# RedpiLite.net
KiCad netlist of a schematic drawn in EAGLE
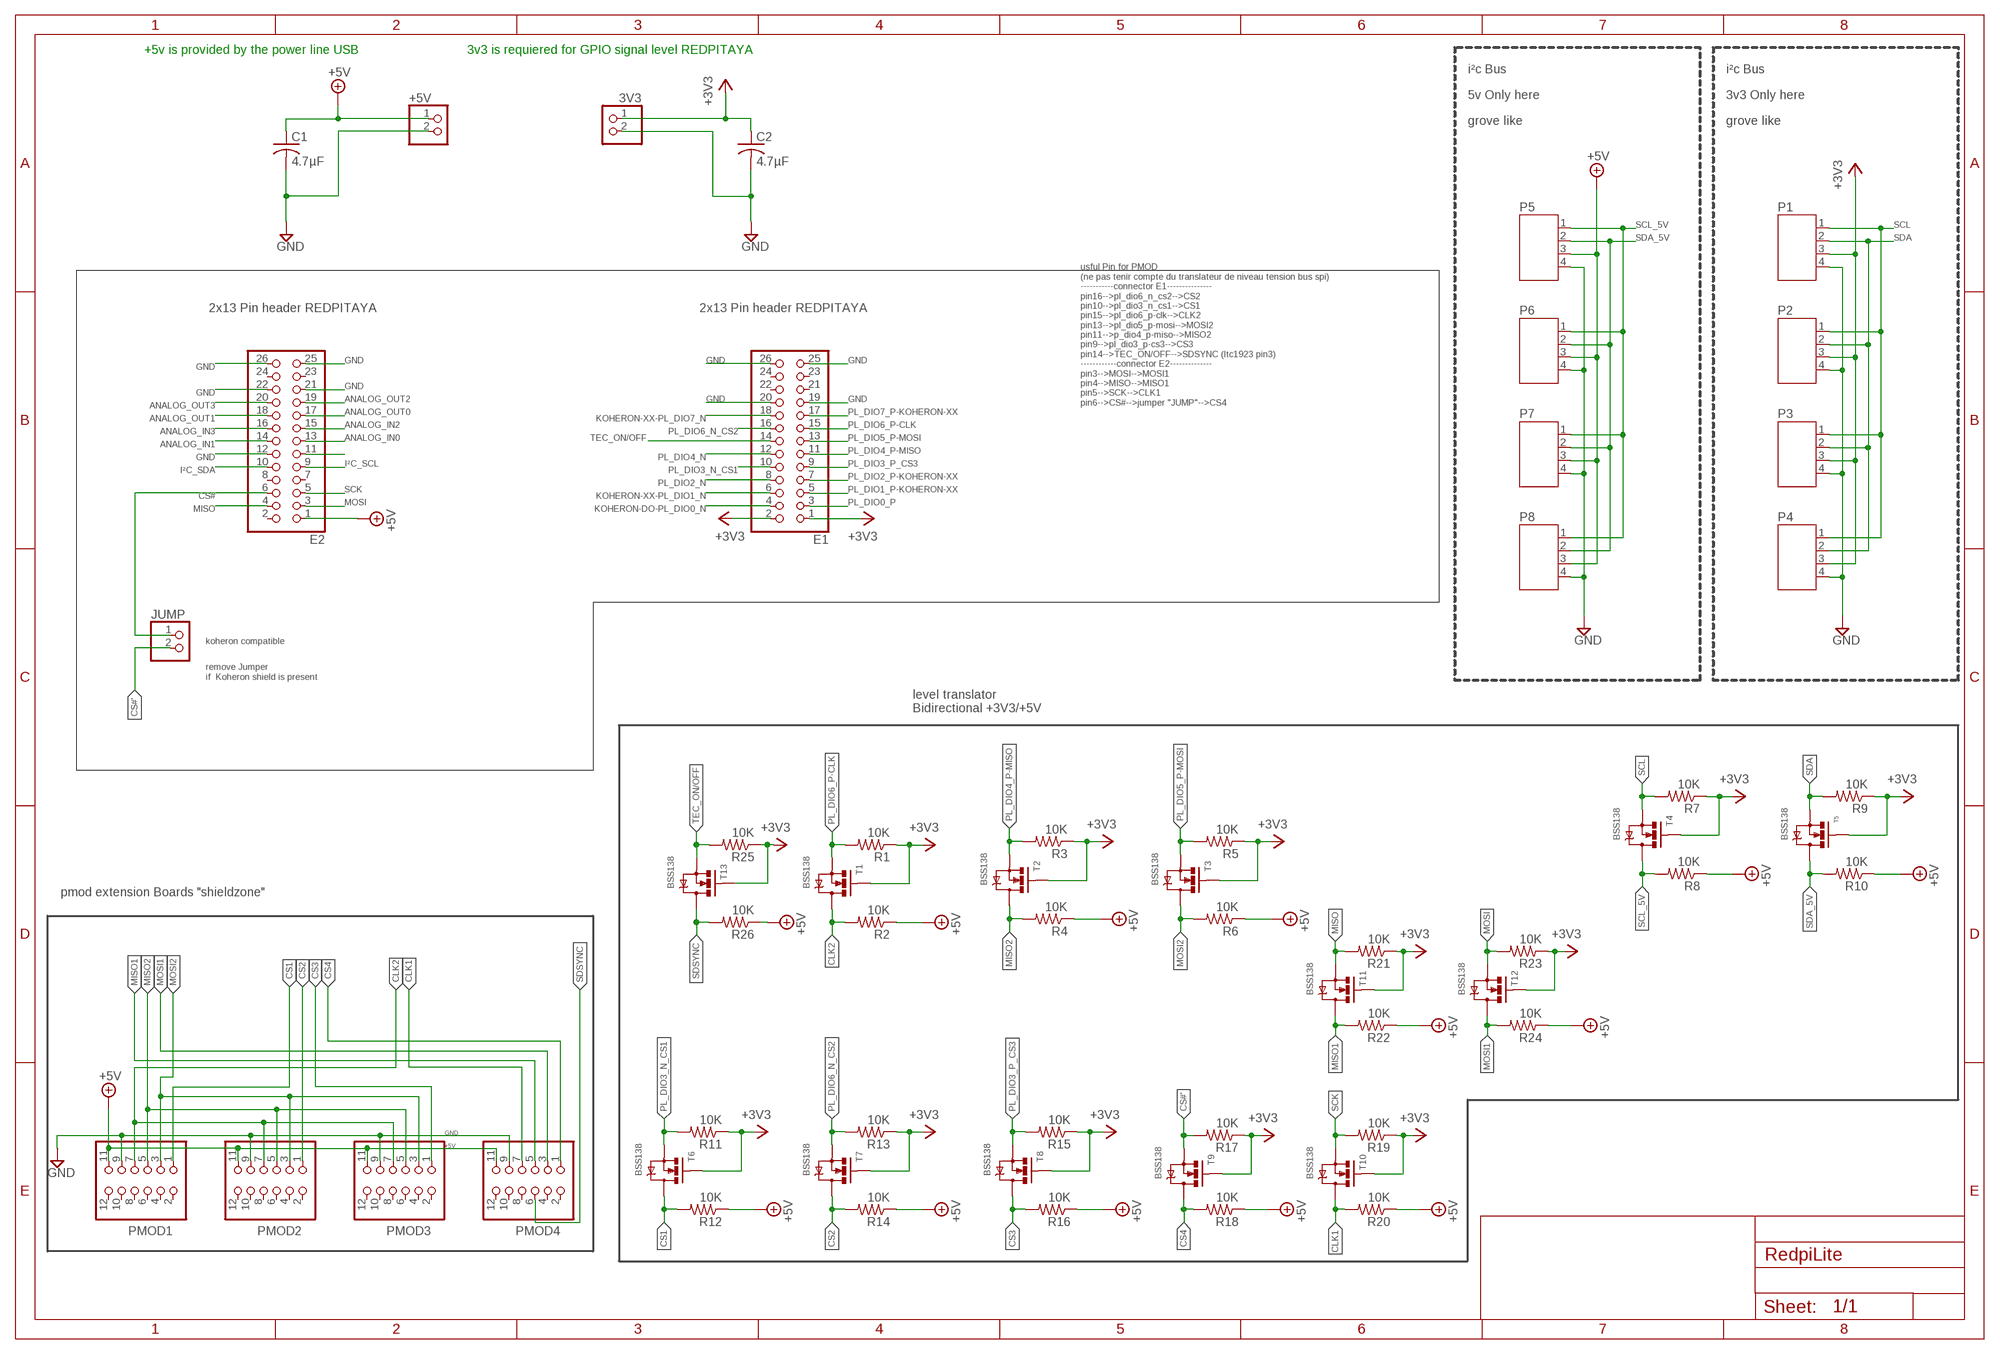
[diagram p0: schematic, sheet 1]

(export (version "E")
  (design (tool "Eeschema 10.0.6"))
  (components
    (comp (ref "+5V")
      (value "PINHD-1X2")
      (footprint "eagle-import:1X02")
      (libsource (lib "eagle-import") (part "PINHD-1X2"))
    )
    (comp (ref "3V3")
      (value "PINHD-1X2")
      (footprint "eagle-import:1X02")
      (libsource (lib "eagle-import") (part "PINHD-1X2"))
    )
    (comp (ref "C1")
      (value "4.7µF")
      (footprint "eagle-import:C1206")
      (libsource (lib "eagle-import") (part "C-USC1206"))
    )
    (comp (ref "C2")
      (value "4.7µF")
      (footprint "eagle-import:C1206")
      (libsource (lib "eagle-import") (part "C-USC1206"))
    )
    (comp (ref "E1")
      (value "PINHD-2X13")
      (footprint "eagle-import:2X13")
      (libsource (lib "eagle-import") (part "PINHD-2X13"))
    )
    (comp (ref "E2")
      (value "PINHD-2X13")
      (footprint "eagle-import:2X13")
      (libsource (lib "eagle-import") (part "PINHD-2X13"))
    )
    (comp (ref "JUMP")
      (value "PINHD-1X2")
      (footprint "eagle-import:1X02")
      (libsource (lib "eagle-import") (part "PINHD-1X2"))
    )
    (comp (ref "P1")
      (value "JST-PH4GROVE")
      (footprint "eagle-import:JST-PH4")
      (libsource (lib "eagle-import") (part "JST-PH4GROVE"))
    )
    (comp (ref "P2")
      (value "JST-PH4GROVE")
      (footprint "eagle-import:JST-PH4")
      (libsource (lib "eagle-import") (part "JST-PH4GROVE"))
    )
    (comp (ref "P3")
      (value "JST-PH4GROVE")
      (footprint "eagle-import:JST-PH4")
      (libsource (lib "eagle-import") (part "JST-PH4GROVE"))
    )
    (comp (ref "P4")
      (value "JST-PH4GROVE")
      (footprint "eagle-import:JST-PH4")
      (libsource (lib "eagle-import") (part "JST-PH4GROVE"))
    )
    (comp (ref "P5")
      (value "JST-PH4GROVE")
      (footprint "eagle-import:JST-PH4")
      (libsource (lib "eagle-import") (part "JST-PH4GROVE"))
    )
    (comp (ref "P6")
      (value "JST-PH4GROVE")
      (footprint "eagle-import:JST-PH4")
      (libsource (lib "eagle-import") (part "JST-PH4GROVE"))
    )
    (comp (ref "P7")
      (value "JST-PH4GROVE")
      (footprint "eagle-import:JST-PH4")
      (libsource (lib "eagle-import") (part "JST-PH4GROVE"))
    )
    (comp (ref "P8")
      (value "JST-PH4GROVE")
      (footprint "eagle-import:JST-PH4")
      (libsource (lib "eagle-import") (part "JST-PH4GROVE"))
    )
    (comp (ref "PMOD1")
      (value "PINHD-2X6/90")
      (footprint "eagle-import:2X06_90")
      (libsource (lib "eagle-import") (part "PINHD-2X6/90"))
    )
    (comp (ref "PMOD2")
      (value "PINHD-2X6/90")
      (footprint "eagle-import:2X06_90")
      (libsource (lib "eagle-import") (part "PINHD-2X6/90"))
    )
    (comp (ref "PMOD3")
      (value "PINHD-2X6/90")
      (footprint "eagle-import:2X06_90")
      (libsource (lib "eagle-import") (part "PINHD-2X6/90"))
    )
    (comp (ref "PMOD4")
      (value "PINHD-2X6/90")
      (footprint "eagle-import:2X06_90")
      (libsource (lib "eagle-import") (part "PINHD-2X6/90"))
    )
    (comp (ref "R1")
      (value "10K")
      (footprint "eagle-import:0603-RES")
      (libsource (lib "eagle-import") (part "RESISTOR0603-RES"))
    )
    (comp (ref "R2")
      (value "10K")
      (footprint "eagle-import:0603-RES")
      (libsource (lib "eagle-import") (part "RESISTOR0603-RES"))
    )
    (comp (ref "R3")
      (value "10K")
      (footprint "eagle-import:0603-RES")
      (libsource (lib "eagle-import") (part "RESISTOR0603-RES"))
    )
    (comp (ref "R4")
      (value "10K")
      (footprint "eagle-import:0603-RES")
      (libsource (lib "eagle-import") (part "RESISTOR0603-RES"))
    )
    (comp (ref "R5")
      (value "10K")
      (footprint "eagle-import:0603-RES")
      (libsource (lib "eagle-import") (part "RESISTOR0603-RES"))
    )
    (comp (ref "R6")
      (value "10K")
      (footprint "eagle-import:0603-RES")
      (libsource (lib "eagle-import") (part "RESISTOR0603-RES"))
    )
    (comp (ref "R7")
      (value "10K")
      (footprint "eagle-import:0603-RES")
      (libsource (lib "eagle-import") (part "RESISTOR0603-RES"))
    )
    (comp (ref "R8")
      (value "10K")
      (footprint "eagle-import:0603-RES")
      (libsource (lib "eagle-import") (part "RESISTOR0603-RES"))
    )
    (comp (ref "R9")
      (value "10K")
      (footprint "eagle-import:0603-RES")
      (libsource (lib "eagle-import") (part "RESISTOR0603-RES"))
    )
    (comp (ref "R10")
      (value "10K")
      (footprint "eagle-import:0603-RES")
      (libsource (lib "eagle-import") (part "RESISTOR0603-RES"))
    )
    (comp (ref "R11")
      (value "10K")
      (footprint "eagle-import:0603-RES")
      (libsource (lib "eagle-import") (part "RESISTOR0603-RES"))
    )
    (comp (ref "R12")
      (value "10K")
      (footprint "eagle-import:0603-RES")
      (libsource (lib "eagle-import") (part "RESISTOR0603-RES"))
    )
    (comp (ref "R13")
      (value "10K")
      (footprint "eagle-import:0603-RES")
      (libsource (lib "eagle-import") (part "RESISTOR0603-RES"))
    )
    (comp (ref "R14")
      (value "10K")
      (footprint "eagle-import:0603-RES")
      (libsource (lib "eagle-import") (part "RESISTOR0603-RES"))
    )
    (comp (ref "R15")
      (value "10K")
      (footprint "eagle-import:0603-RES")
      (libsource (lib "eagle-import") (part "RESISTOR0603-RES"))
    )
    (comp (ref "R16")
      (value "10K")
      (footprint "eagle-import:0603-RES")
      (libsource (lib "eagle-import") (part "RESISTOR0603-RES"))
    )
    (comp (ref "R17")
      (value "10K")
      (footprint "eagle-import:0603-RES")
      (libsource (lib "eagle-import") (part "RESISTOR0603-RES"))
    )
    (comp (ref "R18")
      (value "10K")
      (footprint "eagle-import:0603-RES")
      (libsource (lib "eagle-import") (part "RESISTOR0603-RES"))
    )
    (comp (ref "R19")
      (value "10K")
      (footprint "eagle-import:0603-RES")
      (libsource (lib "eagle-import") (part "RESISTOR0603-RES"))
    )
    (comp (ref "R20")
      (value "10K")
      (footprint "eagle-import:0603-RES")
      (libsource (lib "eagle-import") (part "RESISTOR0603-RES"))
    )
    (comp (ref "R21")
      (value "10K")
      (footprint "eagle-import:0603-RES")
      (libsource (lib "eagle-import") (part "RESISTOR0603-RES"))
    )
    (comp (ref "R22")
      (value "10K")
      (footprint "eagle-import:0603-RES")
      (libsource (lib "eagle-import") (part "RESISTOR0603-RES"))
    )
    (comp (ref "R23")
      (value "10K")
      (footprint "eagle-import:0603-RES")
      (libsource (lib "eagle-import") (part "RESISTOR0603-RES"))
    )
    (comp (ref "R24")
      (value "10K")
      (footprint "eagle-import:0603-RES")
      (libsource (lib "eagle-import") (part "RESISTOR0603-RES"))
    )
    (comp (ref "R25")
      (value "10K")
      (footprint "eagle-import:0603-RES")
      (libsource (lib "eagle-import") (part "RESISTOR0603-RES"))
    )
    (comp (ref "R26")
      (value "10K")
      (footprint "eagle-import:0603-RES")
      (libsource (lib "eagle-import") (part "RESISTOR0603-RES"))
    )
    (comp (ref "T1")
      (value "BSS138")
      (footprint "eagle-import:SOT23-3")
      (libsource (lib "eagle-import") (part "MOSFET-NCHANNELSMD"))
    )
    (comp (ref "T2")
      (value "BSS138")
      (footprint "eagle-import:SOT23-3")
      (libsource (lib "eagle-import") (part "MOSFET-NCHANNELSMD"))
    )
    (comp (ref "T3")
      (value "BSS138")
      (footprint "eagle-import:SOT23-3")
      (libsource (lib "eagle-import") (part "MOSFET-NCHANNELSMD"))
    )
    (comp (ref "T4")
      (value "BSS138")
      (footprint "eagle-import:SOT23-3")
      (libsource (lib "eagle-import") (part "MOSFET-NCHANNELSMD"))
    )
    (comp (ref "T5")
      (value "BSS138")
      (footprint "eagle-import:SOT23-3")
      (libsource (lib "eagle-import") (part "MOSFET-NCHANNELSMD"))
    )
    (comp (ref "T6")
      (value "BSS138")
      (footprint "eagle-import:SOT23-3")
      (libsource (lib "eagle-import") (part "MOSFET-NCHANNELSMD"))
    )
    (comp (ref "T7")
      (value "BSS138")
      (footprint "eagle-import:SOT23-3")
      (libsource (lib "eagle-import") (part "MOSFET-NCHANNELSMD"))
    )
    (comp (ref "T8")
      (value "BSS138")
      (footprint "eagle-import:SOT23-3")
      (libsource (lib "eagle-import") (part "MOSFET-NCHANNELSMD"))
    )
    (comp (ref "T9")
      (value "BSS138")
      (footprint "eagle-import:SOT23-3")
      (libsource (lib "eagle-import") (part "MOSFET-NCHANNELSMD"))
    )
    (comp (ref "T10")
      (value "BSS138")
      (footprint "eagle-import:SOT23-3")
      (libsource (lib "eagle-import") (part "MOSFET-NCHANNELSMD"))
    )
    (comp (ref "T11")
      (value "BSS138")
      (footprint "eagle-import:SOT23-3")
      (libsource (lib "eagle-import") (part "MOSFET-NCHANNELSMD"))
    )
    (comp (ref "T12")
      (value "BSS138")
      (footprint "eagle-import:SOT23-3")
      (libsource (lib "eagle-import") (part "MOSFET-NCHANNELSMD"))
    )
    (comp (ref "T13")
      (value "BSS138")
      (footprint "eagle-import:SOT23-3")
      (libsource (lib "eagle-import") (part "MOSFET-NCHANNELSMD"))
    )
  )
  (nets
    (net (code "1") (name "+3V3") (class "Default")
      (node (ref "3V3") (pin "1") (pinfunction "1_1") (pintype "passive"))
      (node (ref "C2") (pin "1") (pinfunction "1_1") (pintype "passive"))
      (node (ref "E1") (pin "1") (pinfunction "1_1") (pintype "passive"))
      (node (ref "E1") (pin "2") (pinfunction "2_2") (pintype "passive"))
      (node (ref "P1") (pin "3") (pinfunction "3_3") (pintype "passive"))
      (node (ref "P2") (pin "3") (pinfunction "3_3") (pintype "passive"))
      (node (ref "P3") (pin "3") (pinfunction "3_3") (pintype "passive"))
      (node (ref "P4") (pin "3") (pinfunction "3_3") (pintype "passive"))
      (node (ref "R1") (pin "1") (pinfunction "1_1") (pintype "passive"))
      (node (ref "R11") (pin "1") (pinfunction "1_1") (pintype "passive"))
      (node (ref "R13") (pin "1") (pinfunction "1_1") (pintype "passive"))
      (node (ref "R15") (pin "1") (pinfunction "1_1") (pintype "passive"))
      (node (ref "R17") (pin "1") (pinfunction "1_1") (pintype "passive"))
      (node (ref "R19") (pin "1") (pinfunction "1_1") (pintype "passive"))
      (node (ref "R21") (pin "1") (pinfunction "1_1") (pintype "passive"))
      (node (ref "R23") (pin "1") (pinfunction "1_1") (pintype "passive"))
      (node (ref "R25") (pin "1") (pinfunction "1_1") (pintype "passive"))
      (node (ref "R3") (pin "1") (pinfunction "1_1") (pintype "passive"))
      (node (ref "R5") (pin "1") (pinfunction "1_1") (pintype "passive"))
      (node (ref "R7") (pin "1") (pinfunction "1_1") (pintype "passive"))
      (node (ref "R9") (pin "1") (pinfunction "1_1") (pintype "passive"))
      (node (ref "T1") (pin "1") (pinfunction "G_1") (pintype "passive"))
      (node (ref "T10") (pin "1") (pinfunction "G_1") (pintype "passive"))
      (node (ref "T11") (pin "1") (pinfunction "G_1") (pintype "passive"))
      (node (ref "T12") (pin "1") (pinfunction "G_1") (pintype "passive"))
      (node (ref "T13") (pin "1") (pinfunction "G_1") (pintype "passive"))
      (node (ref "T2") (pin "1") (pinfunction "G_1") (pintype "passive"))
      (node (ref "T3") (pin "1") (pinfunction "G_1") (pintype "passive"))
      (node (ref "T4") (pin "1") (pinfunction "G_1") (pintype "passive"))
      (node (ref "T5") (pin "1") (pinfunction "G_1") (pintype "passive"))
      (node (ref "T6") (pin "1") (pinfunction "G_1") (pintype "passive"))
      (node (ref "T7") (pin "1") (pinfunction "G_1") (pintype "passive"))
      (node (ref "T8") (pin "1") (pinfunction "G_1") (pintype "passive"))
      (node (ref "T9") (pin "1") (pinfunction "G_1") (pintype "passive"))
    )
    (net (code "2") (name "+5V") (class "Default")
      (node (ref "+5V") (pin "1") (pinfunction "1_1") (pintype "passive"))
      (node (ref "C1") (pin "1") (pinfunction "1_1") (pintype "passive"))
      (node (ref "E2") (pin "1") (pinfunction "1_1") (pintype "passive"))
      (node (ref "P5") (pin "3") (pinfunction "3_3") (pintype "passive"))
      (node (ref "P6") (pin "3") (pinfunction "3_3") (pintype "passive"))
      (node (ref "P7") (pin "3") (pinfunction "3_3") (pintype "passive"))
      (node (ref "P8") (pin "3") (pinfunction "3_3") (pintype "passive"))
      (node (ref "PMOD1") (pin "11") (pinfunction "11_11") (pintype "passive"))
      (node (ref "PMOD2") (pin "11") (pinfunction "11_11") (pintype "passive"))
      (node (ref "PMOD3") (pin "11") (pinfunction "11_11") (pintype "passive"))
      (node (ref "PMOD4") (pin "11") (pinfunction "11_11") (pintype "passive"))
      (node (ref "R10") (pin "1") (pinfunction "1_1") (pintype "passive"))
      (node (ref "R12") (pin "1") (pinfunction "1_1") (pintype "passive"))
      (node (ref "R14") (pin "1") (pinfunction "1_1") (pintype "passive"))
      (node (ref "R16") (pin "1") (pinfunction "1_1") (pintype "passive"))
      (node (ref "R18") (pin "1") (pinfunction "1_1") (pintype "passive"))
      (node (ref "R2") (pin "1") (pinfunction "1_1") (pintype "passive"))
      (node (ref "R20") (pin "1") (pinfunction "1_1") (pintype "passive"))
      (node (ref "R22") (pin "1") (pinfunction "1_1") (pintype "passive"))
      (node (ref "R24") (pin "1") (pinfunction "1_1") (pintype "passive"))
      (node (ref "R26") (pin "1") (pinfunction "1_1") (pintype "passive"))
      (node (ref "R4") (pin "1") (pinfunction "1_1") (pintype "passive"))
      (node (ref "R6") (pin "1") (pinfunction "1_1") (pintype "passive"))
      (node (ref "R8") (pin "1") (pinfunction "1_1") (pintype "passive"))
    )
    (net (code "3") (name "/ANALOG_IN0") (class "Default")
      (node (ref "E2") (pin "13") (pinfunction "13_13") (pintype "passive"))
    )
    (net (code "4") (name "/ANALOG_IN1") (class "Default")
      (node (ref "E2") (pin "14") (pinfunction "14_14") (pintype "passive"))
    )
    (net (code "5") (name "/ANALOG_IN2") (class "Default")
      (node (ref "E2") (pin "15") (pinfunction "15_15") (pintype "passive"))
    )
    (net (code "6") (name "/ANALOG_IN3") (class "Default")
      (node (ref "E2") (pin "16") (pinfunction "16_16") (pintype "passive"))
    )
    (net (code "7") (name "/ANALOG_OUT0") (class "Default")
      (node (ref "E2") (pin "17") (pinfunction "17_17") (pintype "passive"))
    )
    (net (code "8") (name "/ANALOG_OUT1") (class "Default")
      (node (ref "E2") (pin "18") (pinfunction "18_18") (pintype "passive"))
    )
    (net (code "9") (name "/ANALOG_OUT2") (class "Default")
      (node (ref "E2") (pin "19") (pinfunction "19_19") (pintype "passive"))
    )
    (net (code "10") (name "/ANALOG_OUT3") (class "Default")
      (node (ref "E2") (pin "20") (pinfunction "20_20") (pintype "passive"))
    )
    (net (code "11") (name "/CS#") (class "Default")
      (node (ref "E2") (pin "6") (pinfunction "6_6") (pintype "passive"))
      (node (ref "JUMP") (pin "1") (pinfunction "1_1") (pintype "passive"))
    )
    (net (code "12") (name "/I²C_SCL") (class "Default")
      (node (ref "E2") (pin "9") (pinfunction "9_9") (pintype "passive"))
    )
    (net (code "13") (name "/I²C_SDA") (class "Default")
      (node (ref "E2") (pin "10") (pinfunction "10_10") (pintype "passive"))
    )
    (net (code "14") (name "/KOHERON-DO-PL_DIO0_N") (class "Default")
      (node (ref "E1") (pin "4") (pinfunction "4_4") (pintype "passive"))
    )
    (net (code "15") (name "/KOHERON-XX-PL_DIO1_N") (class "Default")
      (node (ref "E1") (pin "6") (pinfunction "6_6") (pintype "passive"))
    )
    (net (code "16") (name "/KOHERON-XX-PL_DIO7_N") (class "Default")
      (node (ref "E1") (pin "18") (pinfunction "18_18") (pintype "passive"))
    )
    (net (code "17") (name "/PL_DIO0_P") (class "Default")
      (node (ref "E1") (pin "3") (pinfunction "3_3") (pintype "passive"))
    )
    (net (code "18") (name "/PL_DIO1_P-KOHERON-XX") (class "Default")
      (node (ref "E1") (pin "5") (pinfunction "5_5") (pintype "passive"))
    )
    (net (code "19") (name "/PL_DIO2_N") (class "Default")
      (node (ref "E1") (pin "8") (pinfunction "8_8") (pintype "passive"))
    )
    (net (code "20") (name "/PL_DIO2_P-KOHERON-XX") (class "Default")
      (node (ref "E1") (pin "7") (pinfunction "7_7") (pintype "passive"))
    )
    (net (code "21") (name "/PL_DIO4_N") (class "Default")
      (node (ref "E1") (pin "12") (pinfunction "12_12") (pintype "passive"))
    )
    (net (code "22") (name "/PL_DIO7_P-KOHERON-XX") (class "Default")
      (node (ref "E1") (pin "17") (pinfunction "17_17") (pintype "passive"))
    )
    (net (code "23") (name "CLK1") (class "Default")
      (node (ref "PMOD4") (pin "7") (pinfunction "7_7") (pintype "passive"))
      (node (ref "R20") (pin "2") (pinfunction "2_2") (pintype "passive"))
      (node (ref "T10") (pin "3") (pinfunction "D_3") (pintype "passive"))
    )
    (net (code "24") (name "CLK2") (class "Default")
      (node (ref "PMOD1") (pin "7") (pinfunction "7_7") (pintype "passive"))
      (node (ref "PMOD2") (pin "7") (pinfunction "7_7") (pintype "passive"))
      (node (ref "PMOD3") (pin "7") (pinfunction "7_7") (pintype "passive"))
      (node (ref "R2") (pin "2") (pinfunction "2_2") (pintype "passive"))
      (node (ref "T1") (pin "3") (pinfunction "D_3") (pintype "passive"))
    )
    (net (code "25") (name "CS#'") (class "Default")
      (node (ref "JUMP") (pin "2") (pinfunction "2_2") (pintype "passive"))
      (node (ref "R17") (pin "2") (pinfunction "2_2") (pintype "passive"))
      (node (ref "T9") (pin "2") (pinfunction "S_2") (pintype "passive"))
    )
    (net (code "26") (name "CS1") (class "Default")
      (node (ref "PMOD1") (pin "1") (pinfunction "1_1") (pintype "passive"))
      (node (ref "R12") (pin "2") (pinfunction "2_2") (pintype "passive"))
      (node (ref "T6") (pin "3") (pinfunction "D_3") (pintype "passive"))
    )
    (net (code "27") (name "CS2") (class "Default")
      (node (ref "PMOD2") (pin "1") (pinfunction "1_1") (pintype "passive"))
      (node (ref "R14") (pin "2") (pinfunction "2_2") (pintype "passive"))
      (node (ref "T7") (pin "3") (pinfunction "D_3") (pintype "passive"))
    )
    (net (code "28") (name "CS3") (class "Default")
      (node (ref "PMOD3") (pin "1") (pinfunction "1_1") (pintype "passive"))
      (node (ref "R16") (pin "2") (pinfunction "2_2") (pintype "passive"))
      (node (ref "T8") (pin "3") (pinfunction "D_3") (pintype "passive"))
    )
    (net (code "29") (name "CS4") (class "Default")
      (node (ref "PMOD4") (pin "1") (pinfunction "1_1") (pintype "passive"))
      (node (ref "R18") (pin "2") (pinfunction "2_2") (pintype "passive"))
      (node (ref "T9") (pin "3") (pinfunction "D_3") (pintype "passive"))
    )
    (net (code "30") (name "GND") (class "Default")
      (node (ref "+5V") (pin "2") (pinfunction "2_2") (pintype "passive"))
      (node (ref "3V3") (pin "2") (pinfunction "2_2") (pintype "passive"))
      (node (ref "C1") (pin "2") (pinfunction "2_2") (pintype "passive"))
      (node (ref "C2") (pin "2") (pinfunction "2_2") (pintype "passive"))
      (node (ref "E1") (pin "19") (pinfunction "19_19") (pintype "passive"))
      (node (ref "E1") (pin "20") (pinfunction "20_20") (pintype "passive"))
      (node (ref "E1") (pin "25") (pinfunction "25_25") (pintype "passive"))
      (node (ref "E1") (pin "26") (pinfunction "26_26") (pintype "passive"))
      (node (ref "E2") (pin "12") (pinfunction "12_12") (pintype "passive"))
      (node (ref "E2") (pin "21") (pinfunction "21_21") (pintype "passive"))
      (node (ref "E2") (pin "22") (pinfunction "22_22") (pintype "passive"))
      (node (ref "E2") (pin "25") (pinfunction "25_25") (pintype "passive"))
      (node (ref "E2") (pin "26") (pinfunction "26_26") (pintype "passive"))
      (node (ref "P1") (pin "4") (pinfunction "4_4") (pintype "passive"))
      (node (ref "P2") (pin "4") (pinfunction "4_4") (pintype "passive"))
      (node (ref "P3") (pin "4") (pinfunction "4_4") (pintype "passive"))
      (node (ref "P4") (pin "4") (pinfunction "4_4") (pintype "passive"))
      (node (ref "P5") (pin "4") (pinfunction "4_4") (pintype "passive"))
      (node (ref "P6") (pin "4") (pinfunction "4_4") (pintype "passive"))
      (node (ref "P7") (pin "4") (pinfunction "4_4") (pintype "passive"))
      (node (ref "P8") (pin "4") (pinfunction "4_4") (pintype "passive"))
      (node (ref "PMOD1") (pin "9") (pinfunction "9_9") (pintype "passive"))
      (node (ref "PMOD2") (pin "9") (pinfunction "9_9") (pintype "passive"))
      (node (ref "PMOD3") (pin "9") (pinfunction "9_9") (pintype "passive"))
      (node (ref "PMOD4") (pin "9") (pinfunction "9_9") (pintype "passive"))
    )
    (net (code "31") (name "MISO") (class "Default")
      (node (ref "E2") (pin "4") (pinfunction "4_4") (pintype "passive"))
      (node (ref "R21") (pin "2") (pinfunction "2_2") (pintype "passive"))
      (node (ref "T11") (pin "2") (pinfunction "S_2") (pintype "passive"))
    )
    (net (code "32") (name "MISO1") (class "Default")
      (node (ref "PMOD4") (pin "5") (pinfunction "5_5") (pintype "passive"))
      (node (ref "R22") (pin "2") (pinfunction "2_2") (pintype "passive"))
      (node (ref "T11") (pin "3") (pinfunction "D_3") (pintype "passive"))
    )
    (net (code "33") (name "MISO2") (class "Default")
      (node (ref "PMOD1") (pin "5") (pinfunction "5_5") (pintype "passive"))
      (node (ref "PMOD2") (pin "5") (pinfunction "5_5") (pintype "passive"))
      (node (ref "PMOD3") (pin "5") (pinfunction "5_5") (pintype "passive"))
      (node (ref "R4") (pin "2") (pinfunction "2_2") (pintype "passive"))
      (node (ref "T2") (pin "3") (pinfunction "D_3") (pintype "passive"))
    )
    (net (code "34") (name "MOSI") (class "Default")
      (node (ref "E2") (pin "3") (pinfunction "3_3") (pintype "passive"))
      (node (ref "R23") (pin "2") (pinfunction "2_2") (pintype "passive"))
      (node (ref "T12") (pin "2") (pinfunction "S_2") (pintype "passive"))
    )
    (net (code "35") (name "MOSI1") (class "Default")
      (node (ref "PMOD4") (pin "3") (pinfunction "3_3") (pintype "passive"))
      (node (ref "R24") (pin "2") (pinfunction "2_2") (pintype "passive"))
      (node (ref "T12") (pin "3") (pinfunction "D_3") (pintype "passive"))
    )
    (net (code "36") (name "MOSI2") (class "Default")
      (node (ref "PMOD1") (pin "3") (pinfunction "3_3") (pintype "passive"))
      (node (ref "PMOD2") (pin "3") (pinfunction "3_3") (pintype "passive"))
      (node (ref "PMOD3") (pin "3") (pinfunction "3_3") (pintype "passive"))
      (node (ref "R6") (pin "2") (pinfunction "2_2") (pintype "passive"))
      (node (ref "T3") (pin "3") (pinfunction "D_3") (pintype "passive"))
    )
    (net (code "37") (name "PL_DIO3_N_CS1") (class "Default")
      (node (ref "E1") (pin "10") (pinfunction "10_10") (pintype "passive"))
      (node (ref "R11") (pin "2") (pinfunction "2_2") (pintype "passive"))
      (node (ref "T6") (pin "2") (pinfunction "S_2") (pintype "passive"))
    )
    (net (code "38") (name "PL_DIO3_P_CS3") (class "Default")
      (node (ref "E1") (pin "9") (pinfunction "9_9") (pintype "passive"))
      (node (ref "R15") (pin "2") (pinfunction "2_2") (pintype "passive"))
      (node (ref "T8") (pin "2") (pinfunction "S_2") (pintype "passive"))
    )
    (net (code "39") (name "PL_DIO4_P-MISO") (class "Default")
      (node (ref "E1") (pin "11") (pinfunction "11_11") (pintype "passive"))
      (node (ref "R3") (pin "2") (pinfunction "2_2") (pintype "passive"))
      (node (ref "T2") (pin "2") (pinfunction "S_2") (pintype "passive"))
    )
    (net (code "40") (name "PL_DIO5_P-MOSI") (class "Default")
      (node (ref "E1") (pin "13") (pinfunction "13_13") (pintype "passive"))
      (node (ref "R5") (pin "2") (pinfunction "2_2") (pintype "passive"))
      (node (ref "T3") (pin "2") (pinfunction "S_2") (pintype "passive"))
    )
    (net (code "41") (name "PL_DIO6_N_CS2") (class "Default")
      (node (ref "E1") (pin "16") (pinfunction "16_16") (pintype "passive"))
      (node (ref "R13") (pin "2") (pinfunction "2_2") (pintype "passive"))
      (node (ref "T7") (pin "2") (pinfunction "S_2") (pintype "passive"))
    )
    (net (code "42") (name "PL_DIO6_P-CLK") (class "Default")
      (node (ref "E1") (pin "15") (pinfunction "15_15") (pintype "passive"))
      (node (ref "R1") (pin "2") (pinfunction "2_2") (pintype "passive"))
      (node (ref "T1") (pin "2") (pinfunction "S_2") (pintype "passive"))
    )
    (net (code "43") (name "SCK") (class "Default")
      (node (ref "E2") (pin "5") (pinfunction "5_5") (pintype "passive"))
      (node (ref "R19") (pin "2") (pinfunction "2_2") (pintype "passive"))
      (node (ref "T10") (pin "2") (pinfunction "S_2") (pintype "passive"))
    )
    (net (code "44") (name "SCL") (class "Default")
      (node (ref "P1") (pin "1") (pinfunction "1_1") (pintype "passive"))
      (node (ref "P2") (pin "1") (pinfunction "1_1") (pintype "passive"))
      (node (ref "P3") (pin "1") (pinfunction "1_1") (pintype "passive"))
      (node (ref "P4") (pin "1") (pinfunction "1_1") (pintype "passive"))
      (node (ref "R7") (pin "2") (pinfunction "2_2") (pintype "passive"))
      (node (ref "T4") (pin "2") (pinfunction "S_2") (pintype "passive"))
    )
    (net (code "45") (name "SCL_5V") (class "Default")
      (node (ref "P5") (pin "1") (pinfunction "1_1") (pintype "passive"))
      (node (ref "P6") (pin "1") (pinfunction "1_1") (pintype "passive"))
      (node (ref "P7") (pin "1") (pinfunction "1_1") (pintype "passive"))
      (node (ref "P8") (pin "1") (pinfunction "1_1") (pintype "passive"))
      (node (ref "R8") (pin "2") (pinfunction "2_2") (pintype "passive"))
      (node (ref "T4") (pin "3") (pinfunction "D_3") (pintype "passive"))
    )
    (net (code "46") (name "SDA") (class "Default")
      (node (ref "P1") (pin "2") (pinfunction "2_2") (pintype "passive"))
      (node (ref "P2") (pin "2") (pinfunction "2_2") (pintype "passive"))
      (node (ref "P3") (pin "2") (pinfunction "2_2") (pintype "passive"))
      (node (ref "P4") (pin "2") (pinfunction "2_2") (pintype "passive"))
      (node (ref "R9") (pin "2") (pinfunction "2_2") (pintype "passive"))
      (node (ref "T5") (pin "2") (pinfunction "S_2") (pintype "passive"))
    )
    (net (code "47") (name "SDA_5V") (class "Default")
      (node (ref "P5") (pin "2") (pinfunction "2_2") (pintype "passive"))
      (node (ref "P6") (pin "2") (pinfunction "2_2") (pintype "passive"))
      (node (ref "P7") (pin "2") (pinfunction "2_2") (pintype "passive"))
      (node (ref "P8") (pin "2") (pinfunction "2_2") (pintype "passive"))
      (node (ref "R10") (pin "2") (pinfunction "2_2") (pintype "passive"))
      (node (ref "T5") (pin "3") (pinfunction "D_3") (pintype "passive"))
    )
    (net (code "48") (name "SDSYNC") (class "Default")
      (node (ref "PMOD4") (pin "6") (pinfunction "6_6") (pintype "passive"))
      (node (ref "R26") (pin "2") (pinfunction "2_2") (pintype "passive"))
      (node (ref "T13") (pin "3") (pinfunction "D_3") (pintype "passive"))
    )
    (net (code "49") (name "TEC_ON{slash}OFF") (class "Default")
      (node (ref "E1") (pin "14") (pinfunction "14_14") (pintype "passive"))
      (node (ref "R25") (pin "2") (pinfunction "2_2") (pintype "passive"))
      (node (ref "T13") (pin "2") (pinfunction "S_2") (pintype "passive"))
    )
    (net (code "50") (name "unconnected-(E1-Pad21)") (class "Default")
      (node (ref "E1") (pin "21") (pinfunction "21_21") (pintype "passive"))
    )
    (net (code "51") (name "unconnected-(E1-Pad22)") (class "Default")
      (node (ref "E1") (pin "22") (pinfunction "22_22") (pintype "passive"))
    )
    (net (code "52") (name "unconnected-(E1-Pad23)") (class "Default")
      (node (ref "E1") (pin "23") (pinfunction "23_23") (pintype "passive"))
    )
    (net (code "53") (name "unconnected-(E1-Pad24)") (class "Default")
      (node (ref "E1") (pin "24") (pinfunction "24_24") (pintype "passive"))
    )
    (net (code "54") (name "unconnected-(E2-Pad2)") (class "Default")
      (node (ref "E2") (pin "2") (pinfunction "2_2") (pintype "passive"))
    )
    (net (code "55") (name "unconnected-(E2-Pad7)") (class "Default")
      (node (ref "E2") (pin "7") (pinfunction "7_7") (pintype "passive"))
    )
    (net (code "56") (name "unconnected-(E2-Pad8)") (class "Default")
      (node (ref "E2") (pin "8") (pinfunction "8_8") (pintype "passive"))
    )
    (net (code "57") (name "unconnected-(E2-Pad11)") (class "Default")
      (node (ref "E2") (pin "11") (pinfunction "11_11") (pintype "passive"))
    )
    (net (code "58") (name "unconnected-(E2-Pad23)") (class "Default")
      (node (ref "E2") (pin "23") (pinfunction "23_23") (pintype "passive"))
    )
    (net (code "59") (name "unconnected-(E2-Pad24)") (class "Default")
      (node (ref "E2") (pin "24") (pinfunction "24_24") (pintype "passive"))
    )
    (net (code "60") (name "unconnected-(PMOD1-Pad2)") (class "Default")
      (node (ref "PMOD1") (pin "2") (pinfunction "2_2") (pintype "passive"))
    )
    (net (code "61") (name "unconnected-(PMOD1-Pad4)") (class "Default")
      (node (ref "PMOD1") (pin "4") (pinfunction "4_4") (pintype "passive"))
    )
    (net (code "62") (name "unconnected-(PMOD1-Pad6)") (class "Default")
      (node (ref "PMOD1") (pin "6") (pinfunction "6_6") (pintype "passive"))
    )
    (net (code "63") (name "unconnected-(PMOD1-Pad8)") (class "Default")
      (node (ref "PMOD1") (pin "8") (pinfunction "8_8") (pintype "passive"))
    )
    (net (code "64") (name "unconnected-(PMOD1-Pad10)") (class "Default")
      (node (ref "PMOD1") (pin "10") (pinfunction "10_10") (pintype "passive"))
    )
    (net (code "65") (name "unconnected-(PMOD1-Pad12)") (class "Default")
      (node (ref "PMOD1") (pin "12") (pinfunction "12_12") (pintype "passive"))
    )
    (net (code "66") (name "unconnected-(PMOD2-Pad2)") (class "Default")
      (node (ref "PMOD2") (pin "2") (pinfunction "2_2") (pintype "passive"))
    )
    (net (code "67") (name "unconnected-(PMOD2-Pad4)") (class "Default")
      (node (ref "PMOD2") (pin "4") (pinfunction "4_4") (pintype "passive"))
    )
    (net (code "68") (name "unconnected-(PMOD2-Pad6)") (class "Default")
      (node (ref "PMOD2") (pin "6") (pinfunction "6_6") (pintype "passive"))
    )
    (net (code "69") (name "unconnected-(PMOD2-Pad8)") (class "Default")
      (node (ref "PMOD2") (pin "8") (pinfunction "8_8") (pintype "passive"))
    )
    (net (code "70") (name "unconnected-(PMOD2-Pad10)") (class "Default")
      (node (ref "PMOD2") (pin "10") (pinfunction "10_10") (pintype "passive"))
    )
    (net (code "71") (name "unconnected-(PMOD2-Pad12)") (class "Default")
      (node (ref "PMOD2") (pin "12") (pinfunction "12_12") (pintype "passive"))
    )
    (net (code "72") (name "unconnected-(PMOD3-Pad2)") (class "Default")
      (node (ref "PMOD3") (pin "2") (pinfunction "2_2") (pintype "passive"))
    )
    (net (code "73") (name "unconnected-(PMOD3-Pad4)") (class "Default")
      (node (ref "PMOD3") (pin "4") (pinfunction "4_4") (pintype "passive"))
    )
    (net (code "74") (name "unconnected-(PMOD3-Pad6)") (class "Default")
      (node (ref "PMOD3") (pin "6") (pinfunction "6_6") (pintype "passive"))
    )
    (net (code "75") (name "unconnected-(PMOD3-Pad8)") (class "Default")
      (node (ref "PMOD3") (pin "8") (pinfunction "8_8") (pintype "passive"))
    )
    (net (code "76") (name "unconnected-(PMOD3-Pad10)") (class "Default")
      (node (ref "PMOD3") (pin "10") (pinfunction "10_10") (pintype "passive"))
    )
    (net (code "77") (name "unconnected-(PMOD3-Pad12)") (class "Default")
      (node (ref "PMOD3") (pin "12") (pinfunction "12_12") (pintype "passive"))
    )
    (net (code "78") (name "unconnected-(PMOD4-Pad2)") (class "Default")
      (node (ref "PMOD4") (pin "2") (pinfunction "2_2") (pintype "passive"))
    )
    (net (code "79") (name "unconnected-(PMOD4-Pad4)") (class "Default")
      (node (ref "PMOD4") (pin "4") (pinfunction "4_4") (pintype "passive"))
    )
    (net (code "80") (name "unconnected-(PMOD4-Pad8)") (class "Default")
      (node (ref "PMOD4") (pin "8") (pinfunction "8_8") (pintype "passive"))
    )
    (net (code "81") (name "unconnected-(PMOD4-Pad10)") (class "Default")
      (node (ref "PMOD4") (pin "10") (pinfunction "10_10") (pintype "passive"))
    )
    (net (code "82") (name "unconnected-(PMOD4-Pad12)") (class "Default")
      (node (ref "PMOD4") (pin "12") (pinfunction "12_12") (pintype "passive"))
    )
  )
)
